# mic-input.net
KiCad netlist of a schematic drawn in EAGLE
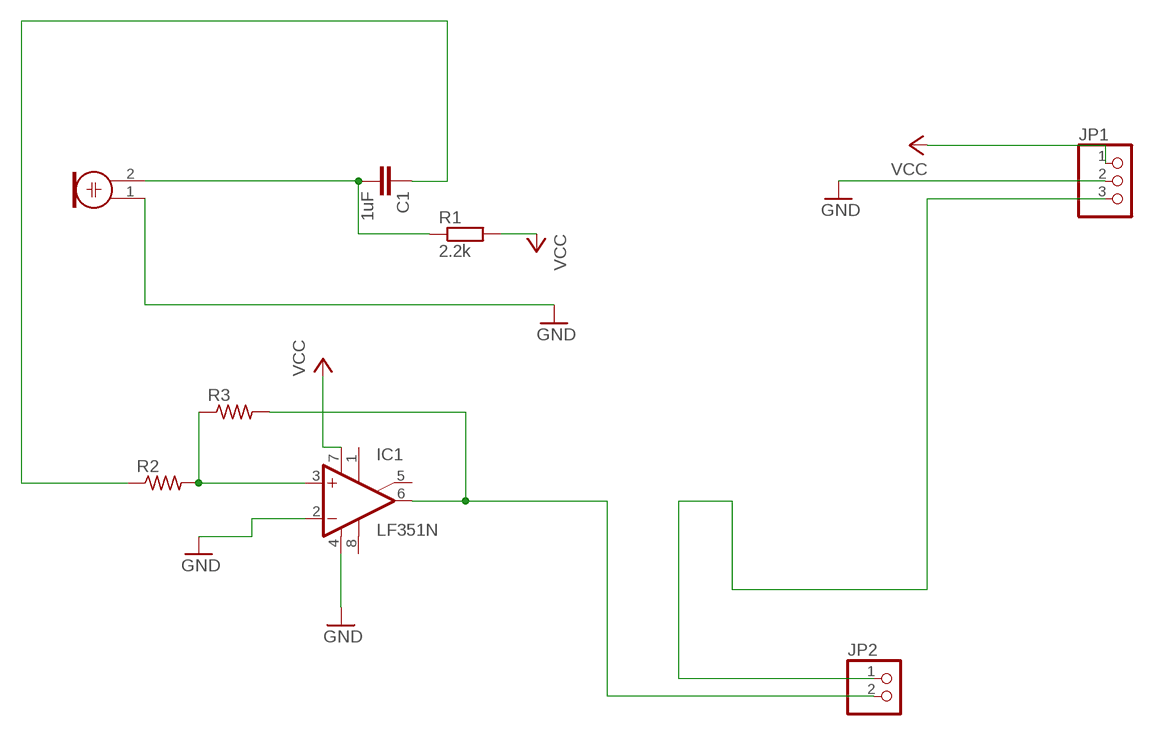
[diagram p0: schematic, sheet 1]

(export (version "E")
  (design (tool "Eeschema 10.0.6"))
  (components
    (comp (ref "C1")
      (value "1uF")
      (footprint "eagle-import:C2.5-3")
      (libsource (lib "eagle-import") (part "C2,5-3"))
    )
    (comp (ref "IC1")
      (value "LF351N")
      (footprint "eagle-import:DIL08")
      (libsource (lib "eagle-import") (part "LF351N"))
    )
    (comp (ref "JP1")
      (value "PINHD-1X3")
      (footprint "eagle-import:1X03")
      (libsource (lib "eagle-import") (part "PINHD-1X3"))
    )
    (comp (ref "JP2")
      (value "PINHD-1X2")
      (footprint "eagle-import:1X02")
      (libsource (lib "eagle-import") (part "PINHD-1X2"))
    )
    (comp (ref "M1")
      (value "ELECTRET_MICROPHON-F6050AP")
      (footprint "eagle-import:F6050AP")
      (libsource (lib "eagle-import") (part "ELECTRET_MICROPHON-F6050AP"))
    )
    (comp (ref "R1")
      (value "2.2k")
      (footprint "eagle-import:0204_7")
      (libsource (lib "eagle-import") (part "R-EU_0204/7"))
    )
    (comp (ref "R2")
      (value "R-US_0204/7")
      (footprint "eagle-import:0204_7")
      (libsource (lib "eagle-import") (part "R-US_0204/7"))
    )
    (comp (ref "R3")
      (value "R-US_0204/7")
      (footprint "eagle-import:0204_7")
      (libsource (lib "eagle-import") (part "R-US_0204/7"))
    )
  )
  (nets
    (net (code "1") (name "GND") (class "Default")
      (node (ref "IC1") (pin "2") (pinfunction "-IN_2") (pintype "input"))
      (node (ref "IC1") (pin "4") (pinfunction "V-_4") (pintype "power_in"))
      (node (ref "JP1") (pin "2") (pinfunction "2_2") (pintype "passive"))
      (node (ref "M1") (pin "1") (pinfunction "1_1") (pintype "passive"))
    )
    (net (code "2") (name "Net-(C1-Pad1)") (class "Default")
      (node (ref "C1") (pin "1") (pinfunction "1_1") (pintype "passive"))
      (node (ref "R2") (pin "1") (pinfunction "1_1") (pintype "passive"))
    )
    (net (code "3") (name "Net-(C1-Pad2)") (class "Default")
      (node (ref "C1") (pin "2") (pinfunction "2_2") (pintype "passive"))
      (node (ref "M1") (pin "2") (pinfunction "2_2") (pintype "passive"))
      (node (ref "R1") (pin "1") (pinfunction "1_1") (pintype "passive"))
    )
    (net (code "4") (name "Net-(IC1-+IN)") (class "Default")
      (node (ref "IC1") (pin "3") (pinfunction "+IN_3") (pintype "input"))
      (node (ref "R2") (pin "2") (pinfunction "2_2") (pintype "passive"))
      (node (ref "R3") (pin "1") (pinfunction "1_1") (pintype "passive"))
    )
    (net (code "5") (name "Net-(IC1-OUT)") (class "Default")
      (node (ref "IC1") (pin "6") (pinfunction "OUT_6") (pintype "output"))
      (node (ref "JP2") (pin "2") (pinfunction "2_2") (pintype "passive"))
      (node (ref "R3") (pin "2") (pinfunction "2_2") (pintype "passive"))
    )
    (net (code "6") (name "Net-(JP1-Pad3)") (class "Default")
      (node (ref "JP1") (pin "3") (pinfunction "3_3") (pintype "passive"))
      (node (ref "JP2") (pin "1") (pinfunction "1_1") (pintype "passive"))
    )
    (net (code "7") (name "VCC") (class "Default")
      (node (ref "IC1") (pin "7") (pinfunction "V+_7") (pintype "power_in"))
      (node (ref "JP1") (pin "1") (pinfunction "1_1") (pintype "passive"))
      (node (ref "R1") (pin "2") (pinfunction "2_2") (pintype "passive"))
    )
    (net (code "8") (name "unconnected-(IC1-ON1-Pad1)") (class "Default")
      (node (ref "IC1") (pin "1") (pinfunction "ON1_1") (pintype "passive"))
    )
    (net (code "9") (name "unconnected-(IC1-ON2-Pad5)") (class "Default")
      (node (ref "IC1") (pin "5") (pinfunction "ON2_5") (pintype "passive"))
    )
    (net (code "10") (name "unconnected-(IC1-OPT-Pad8)") (class "Default")
      (node (ref "IC1") (pin "8") (pinfunction "OPT_8") (pintype "passive"))
    )
  )
)
